# vesc_mcu.net
KiCad netlist of a schematic drawn in Altium Designer
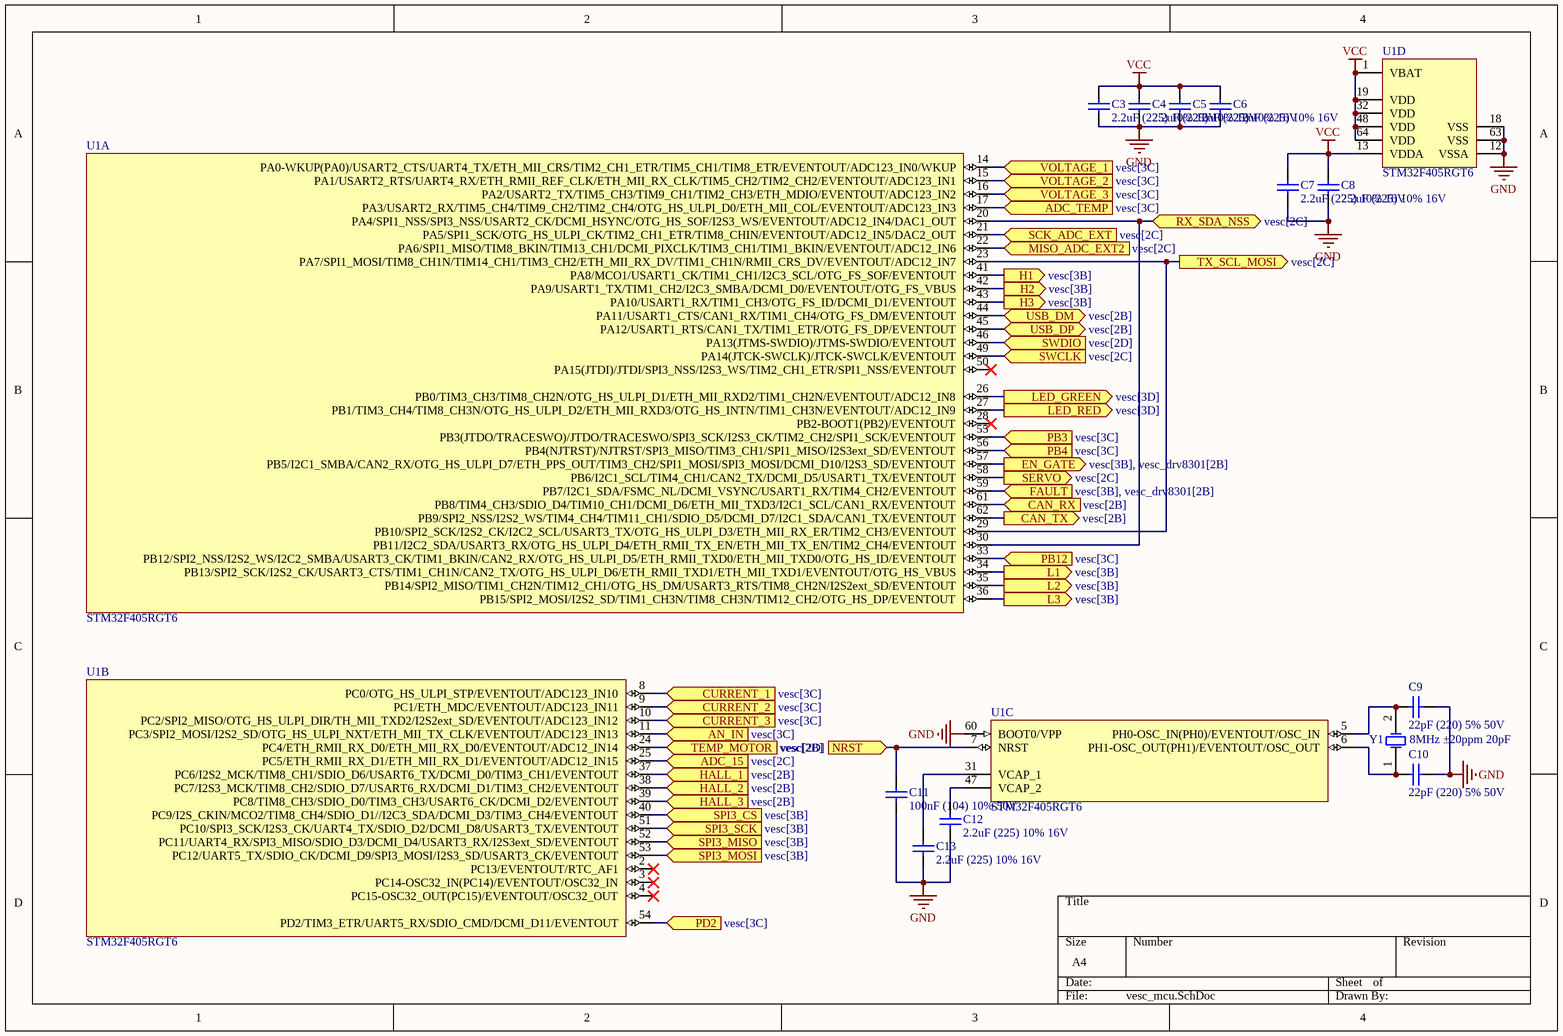
[diagram p0: vesc_mcu.SchDoc]

(export (version "E")
  (design (tool "Eeschema 10.0.6"))
  (components
    (comp (ref "C3")
      (value "2.2uF (225) 10% 16V")
      (footprint "0603_C")
      (description "贴片电容")
      (libsource (lib "Miscellaneous Devices LC") (part "0603 2.2uF (225) 10% 16V"))
    )
    (comp (ref "C4")
      (value "2.2uF (225) 10% 16V")
      (footprint "0603_C")
      (description "贴片电容")
      (libsource (lib "Miscellaneous Devices LC") (part "0603 2.2uF (225) 10% 16V"))
    )
    (comp (ref "C5")
      (value "2.2uF (225) 10% 16V")
      (footprint "0603_C")
      (description "贴片电容")
      (libsource (lib "Miscellaneous Devices LC") (part "0603 2.2uF (225) 10% 16V"))
    )
    (comp (ref "C6")
      (value "2.2uF (225) 10% 16V")
      (footprint "0603_C")
      (description "贴片电容")
      (libsource (lib "Miscellaneous Devices LC") (part "0603 2.2uF (225) 10% 16V"))
    )
    (comp (ref "C7")
      (value "2.2uF (225) 10% 16V")
      (footprint "0603_C")
      (description "贴片电容")
      (libsource (lib "Miscellaneous Devices LC") (part "0603 2.2uF (225) 10% 16V"))
    )
    (comp (ref "C8")
      (value "2.2uF (225) 10% 16V")
      (footprint "0603_C")
      (description "贴片电容")
      (libsource (lib "Miscellaneous Devices LC") (part "0603 2.2uF (225) 10% 16V"))
    )
    (comp (ref "C9")
      (value "22pF (220) 5% 50V")
      (footprint "0603_C")
      (description "贴片电容")
      (libsource (lib "Miscellaneous Devices LC") (part "0603 22pF (220) 5% 50V"))
    )
    (comp (ref "C10")
      (value "22pF (220) 5% 50V")
      (footprint "0603_C")
      (description "贴片电容")
      (libsource (lib "Miscellaneous Devices LC") (part "0603 22pF (220) 5% 50V"))
    )
    (comp (ref "C11")
      (value "100nF (104) 10% 50V")
      (footprint "0603_C")
      (description "贴片电容")
      (libsource (lib "Miscellaneous Devices LC") (part "0603 100nF (104) 10% 50V"))
    )
    (comp (ref "C12")
      (value "2.2uF (225) 10% 16V")
      (footprint "0603_C")
      (description "贴片电容")
      (libsource (lib "Miscellaneous Devices LC") (part "0603 2.2uF (225) 10% 16V"))
    )
    (comp (ref "C13")
      (value "2.2uF (225) 10% 16V")
      (footprint "0603_C")
      (description "贴片电容")
      (libsource (lib "Miscellaneous Devices LC") (part "0603 2.2uF (225) 10% 16V"))
    )
    (comp (ref "U1")
      (value "STM32F405RGT6")
      (footprint "LQFP-64_10x10x05P")
      (description "ARM")
      (libsource (lib "Miscellaneous Devices LC") (part "STM32F405RGT6"))
    )
    (comp (ref "Y1")
      (value "8MHz ±20ppm 20pF")
      (footprint "SMD-5032_2P")
      (description "贴片晶振")
      (libsource (lib "Miscellaneous Devices LC") (part "SMD-5032_2P 8MHz 20ppm 20pF"))
    )
  )
  (nets
    (net (code "1") (name "/ADC_15") (class "Default")
      (node (ref "U1") (pin "25") (pinfunction "PC5/ETH_RMII_RX_D1/ETH_MII_RX_D1/EVENTOUT/ADC12_IN15_25") (pintype "bidirectional"))
    )
    (net (code "2") (name "/ADC_TEMP") (class "Default")
      (node (ref "U1") (pin "17") (pinfunction "PA3/USART2_RX/TIM5_CH4/TIM9_CH2/TIM2_CH4/OTG_HS_ULPI_D0/ETH_MII_COL/EVENTOUT/ADC123_IN3_17") (pintype "bidirectional"))
    )
    (net (code "3") (name "/AN_IN") (class "Default")
      (node (ref "U1") (pin "11") (pinfunction "PC3/SPI2_MOSI/I2S2_SD/OTG_HS_ULPI_NXT/ETH_MII_TX_CLK/EVENTOUT/ADC123_IN13_11") (pintype "bidirectional"))
    )
    (net (code "4") (name "/CAN_RX") (class "Default")
      (node (ref "U1") (pin "61") (pinfunction "PB8/TIM4_CH3/SDIO_D4/TIM10_CH1/DCMI_D6/ETH_MII_TXD3/I2C1_SCL/CAN1_RX/EVENTOUT_61") (pintype "bidirectional"))
    )
    (net (code "5") (name "/CAN_TX") (class "Default")
      (node (ref "U1") (pin "62") (pinfunction "PB9/SPI2_NSS/I2S2_WS/TIM4_CH4/TIM11_CH1/SDIO_D5/DCMI_D7/I2C1_SDA/CAN1_TX/EVENTOUT_62") (pintype "bidirectional"))
    )
    (net (code "6") (name "/CURRENT_1") (class "Default")
      (node (ref "U1") (pin "8") (pinfunction "PC0/OTG_HS_ULPI_STP/EVENTOUT/ADC123_IN10_8") (pintype "bidirectional"))
    )
    (net (code "7") (name "/CURRENT_2") (class "Default")
      (node (ref "U1") (pin "9") (pinfunction "PC1/ETH_MDC/EVENTOUT/ADC123_IN11_9") (pintype "bidirectional"))
    )
    (net (code "8") (name "/CURRENT_3") (class "Default")
      (node (ref "U1") (pin "10") (pinfunction "PC2/SPI2_MISO/OTG_HS_ULPI_DIR/TH_MII_TXD2/I2S2ext_SD/EVENTOUT/ADC123_IN12_10") (pintype "bidirectional"))
    )
    (net (code "9") (name "/EN_GATE") (class "Default")
      (node (ref "U1") (pin "57") (pinfunction "PB5/I2C1_SMBA/CAN2_RX/OTG_HS_ULPI_D7/ETH_PPS_OUT/TIM3_CH2/SPI1_MOSI/SPI3_MOSI/DCMI_D10/I2S3_SD/EVENTOUT_57") (pintype "bidirectional"))
    )
    (net (code "10") (name "/FAULT") (class "Default")
      (node (ref "U1") (pin "59") (pinfunction "PB7/I2C1_SDA/FSMC_NL/DCMI_VSYNC/USART1_RX/TIM4_CH2/EVENTOUT_59") (pintype "bidirectional"))
    )
    (net (code "11") (name "/H1") (class "Default")
      (node (ref "U1") (pin "41") (pinfunction "PA8/MCO1/USART1_CK/TIM1_CH1/I2C3_SCL/OTG_FS_SOF/EVENTOUT_41") (pintype "bidirectional"))
    )
    (net (code "12") (name "/H2") (class "Default")
      (node (ref "U1") (pin "42") (pinfunction "PA9/USART1_TX/TIM1_CH2/I2C3_SMBA/DCMI_D0/EVENTOUT/OTG_FS_VBUS_42") (pintype "bidirectional"))
    )
    (net (code "13") (name "/H3") (class "Default")
      (node (ref "U1") (pin "43") (pinfunction "PA10/USART1_RX/TIM1_CH3/OTG_FS_ID/DCMI_D1/EVENTOUT_43") (pintype "bidirectional"))
    )
    (net (code "14") (name "/HALL_1") (class "Default")
      (node (ref "U1") (pin "37") (pinfunction "PC6/I2S2_MCK/TIM8_CH1/SDIO_D6/USART6_TX/DCMI_D0/TIM3_CH1/EVENTOUT_37") (pintype "bidirectional"))
    )
    (net (code "15") (name "/HALL_2") (class "Default")
      (node (ref "U1") (pin "38") (pinfunction "PC7/I2S3_MCK/TIM8_CH2/SDIO_D7/USART6_RX/DCMI_D1/TIM3_CH2/EVENTOUT_38") (pintype "bidirectional"))
    )
    (net (code "16") (name "/HALL_3") (class "Default")
      (node (ref "U1") (pin "39") (pinfunction "PC8/TIM8_CH3/SDIO_D0/TIM3_CH3/USART6_CK/DCMI_D2/EVENTOUT_39") (pintype "bidirectional"))
    )
    (net (code "17") (name "/L1") (class "Default")
      (node (ref "U1") (pin "34") (pinfunction "PB13/SPI2_SCK/I2S2_CK/USART3_CTS/TIM1_CH1N/CAN2_TX/OTG_HS_ULPI_D6/ETH_RMII_TXD1/ETH_MII_TXD1/EVENTOUT/OTG_HS_VBUS_34") (pintype "bidirectional"))
    )
    (net (code "18") (name "/L2") (class "Default")
      (node (ref "U1") (pin "35") (pinfunction "PB14/SPI2_MISO/TIM1_CH2N/TIM12_CH1/OTG_HS_DM/USART3_RTS/TIM8_CH2N/I2S2ext_SD/EVENTOUT_35") (pintype "bidirectional"))
    )
    (net (code "19") (name "/L3") (class "Default")
      (node (ref "U1") (pin "36") (pinfunction "PB15/SPI2_MOSI/I2S2_SD/TIM1_CH3N/TIM8_CH3N/TIM12_CH2/OTG_HS_DP/EVENTOUT_36") (pintype "bidirectional"))
    )
    (net (code "20") (name "/LED_GREEN") (class "Default")
      (node (ref "U1") (pin "26") (pinfunction "PB0/TIM3_CH3/TIM8_CH2N/OTG_HS_ULPI_D1/ETH_MII_RXD2/TIM1_CH2N/EVENTOUT/ADC12_IN8_26") (pintype "bidirectional"))
    )
    (net (code "21") (name "/LED_RED") (class "Default")
      (node (ref "U1") (pin "27") (pinfunction "PB1/TIM3_CH4/TIM8_CH3N/OTG_HS_ULPI_D2/ETH_MII_RXD3/OTG_HS_INTN/TIM1_CH3N/EVENTOUT/ADC12_IN9_27") (pintype "bidirectional"))
    )
    (net (code "22") (name "/MISO_ADC_EXT2") (class "Default")
      (node (ref "U1") (pin "22") (pinfunction "PA6/SPI1_MISO/TIM8_BKIN/TIM13_CH1/DCMI_PIXCLK/TIM3_CH1/TIM1_BKIN/EVENTOUT/ADC12_IN6_22") (pintype "bidirectional"))
    )
    (net (code "23") (name "/NRST") (class "Default")
      (node (ref "C11") (pin "2") (pinfunction "2_2") (pintype "passive"))
      (node (ref "U1") (pin "7") (pinfunction "NRST_7") (pintype "bidirectional"))
    )
    (net (code "24") (name "/PB3") (class "Default")
      (node (ref "U1") (pin "55") (pinfunction "PB3(JTDO/TRACESWO)/JTDO/TRACESWO/SPI3_SCK/I2S3_CK/TIM2_CH2/SPI1_SCK/EVENTOUT_55") (pintype "bidirectional"))
    )
    (net (code "25") (name "/PB4") (class "Default")
      (node (ref "U1") (pin "56") (pinfunction "PB4(NJTRST)/NJTRST/SPI3_MISO/TIM3_CH1/SPI1_MISO/I2S3ext_SD/EVENTOUT_56") (pintype "bidirectional"))
    )
    (net (code "26") (name "/PB12") (class "Default")
      (node (ref "U1") (pin "33") (pinfunction "PB12/SPI2_NSS/I2S2_WS/I2C2_SMBA/USART3_CK/TIM1_BKIN/CAN2_RX/OTG_HS_ULPI_D5/ETH_RMII_TXD0/ETH_MII_TXD0/OTG_HS_ID/EVENTOUT_33") (pintype "bidirectional"))
    )
    (net (code "27") (name "/PD2") (class "Default")
      (node (ref "U1") (pin "54") (pinfunction "PD2/TIM3_ETR/UART5_RX/SDIO_CMD/DCMI_D11/EVENTOUT_54") (pintype "bidirectional"))
    )
    (net (code "28") (name "/RX_SDA_NSS") (class "Default")
      (node (ref "U1") (pin "20") (pinfunction "PA4/SPI1_NSS/SPI3_NSS/USART2_CK/DCMI_HSYNC/OTG_HS_SOF/I2S3_WS/EVENTOUT/ADC12_IN4/DAC1_OUT_20") (pintype "bidirectional"))
      (node (ref "U1") (pin "30") (pinfunction "PB11/I2C2_SDA/USART3_RX/OTG_HS_ULPI_D4/ETH_RMII_TX_EN/ETH_MII_TX_EN/TIM2_CH4/EVENTOUT_30") (pintype "bidirectional"))
    )
    (net (code "29") (name "/SCK_ADC_EXT") (class "Default")
      (node (ref "U1") (pin "21") (pinfunction "PA5/SPI1_SCK/OTG_HS_ULPI_CK/TIM2_CH1_ETR/TIM8_CHIN/EVENTOUT/ADC12_IN5/DAC2_OUT_21") (pintype "bidirectional"))
    )
    (net (code "30") (name "/SERVO") (class "Default")
      (node (ref "U1") (pin "58") (pinfunction "PB6/I2C1_SCL/TIM4_CH1/CAN2_TX/DCMI_D5/USART1_TX/EVENTOUT_58") (pintype "bidirectional"))
    )
    (net (code "31") (name "/SPI3_CS") (class "Default")
      (node (ref "U1") (pin "40") (pinfunction "PC9/I2S_CKIN/MCO2/TIM8_CH4/SDIO_D1//I2C3_SDA/DCMI_D3/TIM3_CH4/EVENTOUT_40") (pintype "bidirectional"))
    )
    (net (code "32") (name "/SPI3_MISO") (class "Default")
      (node (ref "U1") (pin "52") (pinfunction "PC11/UART4_RX/SPI3_MISO/SDIO_D3/DCMI_D4/USART3_RX/I2S3ext_SD/EVENTOUT_52") (pintype "bidirectional"))
    )
    (net (code "33") (name "/SPI3_MOSI") (class "Default")
      (node (ref "U1") (pin "53") (pinfunction "PC12/UART5_TX/SDIO_CK/DCMI_D9/SPI3_MOSI/I2S3_SD/USART3_CK/EVENTOUT_53") (pintype "bidirectional"))
    )
    (net (code "34") (name "/SPI3_SCK") (class "Default")
      (node (ref "U1") (pin "51") (pinfunction "PC10/SPI3_SCK/I2S3_CK/UART4_TX/SDIO_D2/DCMI_D8/USART3_TX/EVENTOUT_51") (pintype "bidirectional"))
    )
    (net (code "35") (name "/SWCLK") (class "Default")
      (node (ref "U1") (pin "49") (pinfunction "PA14(JTCK-SWCLK)/JTCK-SWCLK/EVENTOUT_49") (pintype "bidirectional"))
    )
    (net (code "36") (name "/SWDIO") (class "Default")
      (node (ref "U1") (pin "46") (pinfunction "PA13(JTMS-SWDIO)/JTMS-SWDIO/EVENTOUT_46") (pintype "bidirectional"))
    )
    (net (code "37") (name "/TEMP_MOTOR") (class "Default")
      (node (ref "U1") (pin "24") (pinfunction "PC4/ETH_RMII_RX_D0/ETH_MII_RX_D0/EVENTOUT/ADC12_IN14_24") (pintype "bidirectional"))
    )
    (net (code "38") (name "/TX_SCL_MOSI") (class "Default")
      (node (ref "U1") (pin "23") (pinfunction "PA7/SPI1_MOSI/TIM8_CH1N/TIM14_CH1/TIM3_CH2/ETH_MII_RX_DV/TIM1_CH1N/RMII_CRS_DV/EVENTOUT/ADC12_IN7_23") (pintype "bidirectional"))
      (node (ref "U1") (pin "29") (pinfunction "PB10/SPI2_SCK/I2S2_CK/I2C2_SCL/USART3_TX/OTG_HS_ULPI_D3/ETH_MII_RX_ER/TIM2_CH3/EVENTOUT_29") (pintype "bidirectional"))
    )
    (net (code "39") (name "/USB_DM") (class "Default")
      (node (ref "U1") (pin "44") (pinfunction "PA11/USART1_CTS/CAN1_RX/TIM1_CH4/OTG_FS_DM/EVENTOUT_44") (pintype "bidirectional"))
    )
    (net (code "40") (name "/USB_DP") (class "Default")
      (node (ref "U1") (pin "45") (pinfunction "PA12/USART1_RTS/CAN1_TX/TIM1_ETR/OTG_FS_DP/EVENTOUT_45") (pintype "bidirectional"))
    )
    (net (code "41") (name "/VOLTAGE_1") (class "Default")
      (node (ref "U1") (pin "14") (pinfunction "PA0-WKUP(PA0)/USART2_CTS/UART4_TX/ETH_MII_CRS/TIM2_CH1_ETR/TIM5_CH1/TIM8_ETR/EVENTOUT/ADC123_IN0/WKUP_14") (pintype "bidirectional"))
    )
    (net (code "42") (name "/VOLTAGE_2") (class "Default")
      (node (ref "U1") (pin "15") (pinfunction "PA1/USART2_RTS/UART4_RX/ETH_RMII_REF_CLK/ETH_MII_RX_CLK/TIM5_CH2/TIM2_CH2/EVENTOUT/ADC123_IN1_15") (pintype "bidirectional"))
    )
    (net (code "43") (name "/VOLTAGE_3") (class "Default")
      (node (ref "U1") (pin "16") (pinfunction "PA2/USART2_TX/TIM5_CH3/TIM9_CH1/TIM2_CH3/ETH_MDIO/EVENTOUT/ADC123_IN2_16") (pintype "bidirectional"))
    )
    (net (code "44") (name "GND") (class "Default")
      (node (ref "C10") (pin "2") (pinfunction "2_2") (pintype "passive"))
      (node (ref "C11") (pin "1") (pinfunction "1_1") (pintype "passive"))
      (node (ref "C12") (pin "1") (pinfunction "1_1") (pintype "passive"))
      (node (ref "C13") (pin "1") (pinfunction "1_1") (pintype "passive"))
      (node (ref "C3") (pin "1") (pinfunction "1_1") (pintype "passive"))
      (node (ref "C4") (pin "1") (pinfunction "1_1") (pintype "passive"))
      (node (ref "C5") (pin "1") (pinfunction "1_1") (pintype "passive"))
      (node (ref "C6") (pin "1") (pinfunction "1_1") (pintype "passive"))
      (node (ref "C7") (pin "1") (pinfunction "1_1") (pintype "passive"))
      (node (ref "C8") (pin "1") (pinfunction "1_1") (pintype "passive"))
      (node (ref "C9") (pin "2") (pinfunction "2_2") (pintype "passive"))
      (node (ref "U1") (pin "12") (pinfunction "VSSA_12") (pintype "power_in"))
      (node (ref "U1") (pin "18") (pinfunction "VSS_18") (pintype "power_in"))
      (node (ref "U1") (pin "60") (pinfunction "BOOT0/VPP_60") (pintype "input"))
      (node (ref "U1") (pin "63") (pinfunction "VSS_63") (pintype "power_in"))
    )
    (net (code "45") (name "Net-(U1C-PH0-OSC_IN(PH0){slash}EVENTOUT{slash}OSC_IN)") (class "Default")
      (node (ref "C9") (pin "1") (pinfunction "1_1") (pintype "passive"))
      (node (ref "U1") (pin "5") (pinfunction "PH0-OSC_IN(PH0)/EVENTOUT/OSC_IN_5") (pintype "bidirectional"))
      (node (ref "Y1") (pin "2") (pinfunction "OSC2_2") (pintype "passive"))
    )
    (net (code "46") (name "Net-(U1C-PH1-OSC_OUT(PH1){slash}EVENTOUT{slash}OSC_OUT)") (class "Default")
      (node (ref "C10") (pin "1") (pinfunction "1_1") (pintype "passive"))
      (node (ref "U1") (pin "6") (pinfunction "PH1-OSC_OUT(PH1)/EVENTOUT/OSC_OUT_6") (pintype "bidirectional"))
      (node (ref "Y1") (pin "1") (pinfunction "OSC1_1") (pintype "passive"))
    )
    (net (code "47") (name "Net-(U1C-VCAP_1)") (class "Default")
      (node (ref "C13") (pin "2") (pinfunction "2_2") (pintype "passive"))
      (node (ref "U1") (pin "31") (pinfunction "VCAP_1_31") (pintype "power_in"))
    )
    (net (code "48") (name "Net-(U1C-VCAP_2)") (class "Default")
      (node (ref "C12") (pin "2") (pinfunction "2_2") (pintype "passive"))
      (node (ref "U1") (pin "47") (pinfunction "VCAP_2_47") (pintype "power_in"))
    )
    (net (code "49") (name "VCC") (class "Default")
      (node (ref "C3") (pin "2") (pinfunction "2_2") (pintype "passive"))
      (node (ref "C4") (pin "2") (pinfunction "2_2") (pintype "passive"))
      (node (ref "C5") (pin "2") (pinfunction "2_2") (pintype "passive"))
      (node (ref "C6") (pin "2") (pinfunction "2_2") (pintype "passive"))
      (node (ref "C7") (pin "2") (pinfunction "2_2") (pintype "passive"))
      (node (ref "C8") (pin "2") (pinfunction "2_2") (pintype "passive"))
      (node (ref "U1") (pin "1") (pinfunction "VBAT_1") (pintype "power_in"))
      (node (ref "U1") (pin "13") (pinfunction "VDDA_13") (pintype "power_in"))
      (node (ref "U1") (pin "19") (pinfunction "VDD_19") (pintype "power_in"))
      (node (ref "U1") (pin "32") (pinfunction "VDD_32") (pintype "power_in"))
      (node (ref "U1") (pin "48") (pinfunction "VDD_48") (pintype "power_in"))
      (node (ref "U1") (pin "64") (pinfunction "VDD_64") (pintype "power_in"))
    )
    (net (code "50") (name "unconnected-(U1A-PA15(JTDI){slash}JTDI{slash}SPI3_NSS{slash}I2S3_WS{slash}TIM2_CH1_ETR{slash}SPI1_NSS{slash}EVENTOUT-Pad50)") (class "Default")
      (node (ref "U1") (pin "50") (pinfunction "PA15(JTDI)/JTDI/SPI3_NSS/I2S3_WS/TIM2_CH1_ETR/SPI1_NSS/EVENTOUT_50") (pintype "bidirectional+no_connect"))
    )
    (net (code "51") (name "unconnected-(U1A-PB2-BOOT1(PB2){slash}EVENTOUT-Pad28)") (class "Default")
      (node (ref "U1") (pin "28") (pinfunction "PB2-BOOT1(PB2)/EVENTOUT_28") (pintype "bidirectional+no_connect"))
    )
    (net (code "52") (name "unconnected-(U1B-PC13{slash}EVENTOUT{slash}RTC_AF1-Pad2)") (class "Default")
      (node (ref "U1") (pin "2") (pinfunction "PC13/EVENTOUT/RTC_AF1_2") (pintype "bidirectional+no_connect"))
    )
    (net (code "53") (name "unconnected-(U1B-PC14-OSC32_IN(PC14){slash}EVENTOUT{slash}OSC32_IN-Pad3)") (class "Default")
      (node (ref "U1") (pin "3") (pinfunction "PC14-OSC32_IN(PC14)/EVENTOUT/OSC32_IN_3") (pintype "bidirectional+no_connect"))
    )
    (net (code "54") (name "unconnected-(U1B-PC15-OSC32_OUT(PC15){slash}EVENTOUT{slash}OSC32_OUT-Pad4)") (class "Default")
      (node (ref "U1") (pin "4") (pinfunction "PC15-OSC32_OUT(PC15)/EVENTOUT/OSC32_OUT_4") (pintype "bidirectional+no_connect"))
    )
  )
)
